# 0X_-_CPU_-_EIM.net
KiCad netlist of a schematic drawn in Altium Designer
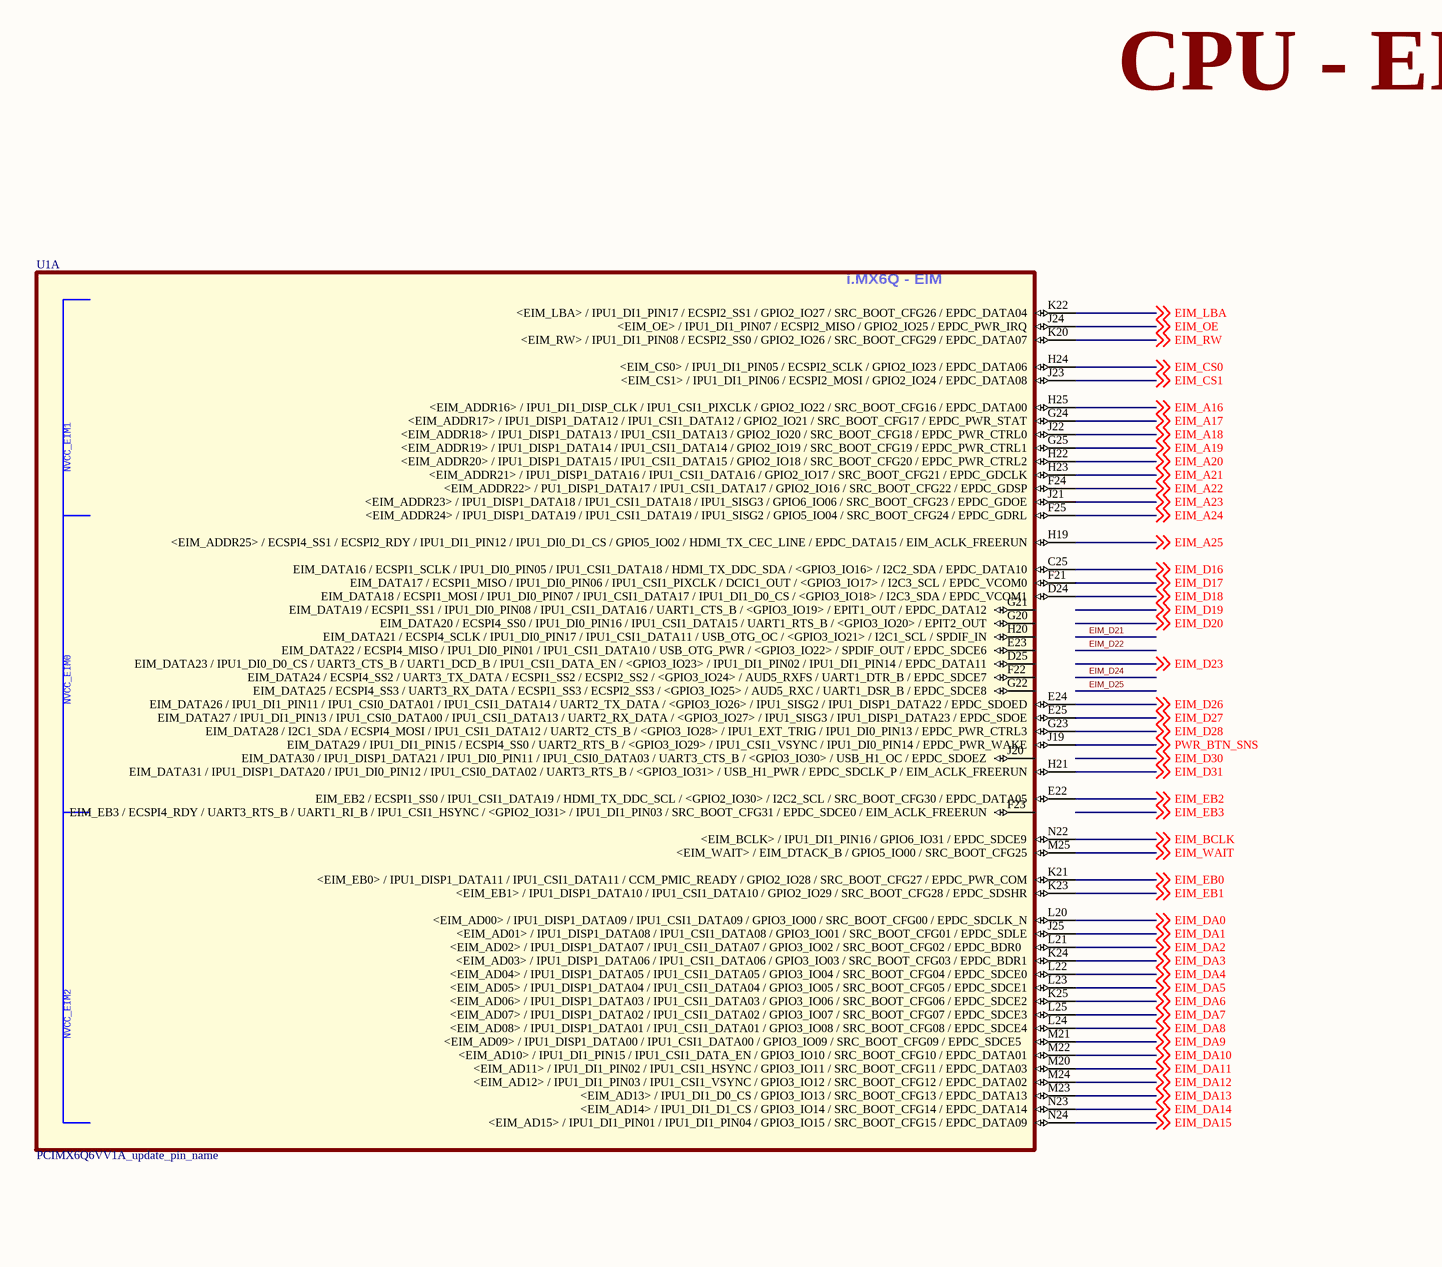
[diagram p0: [0X] - CPU - EIM.SchDoc, left]
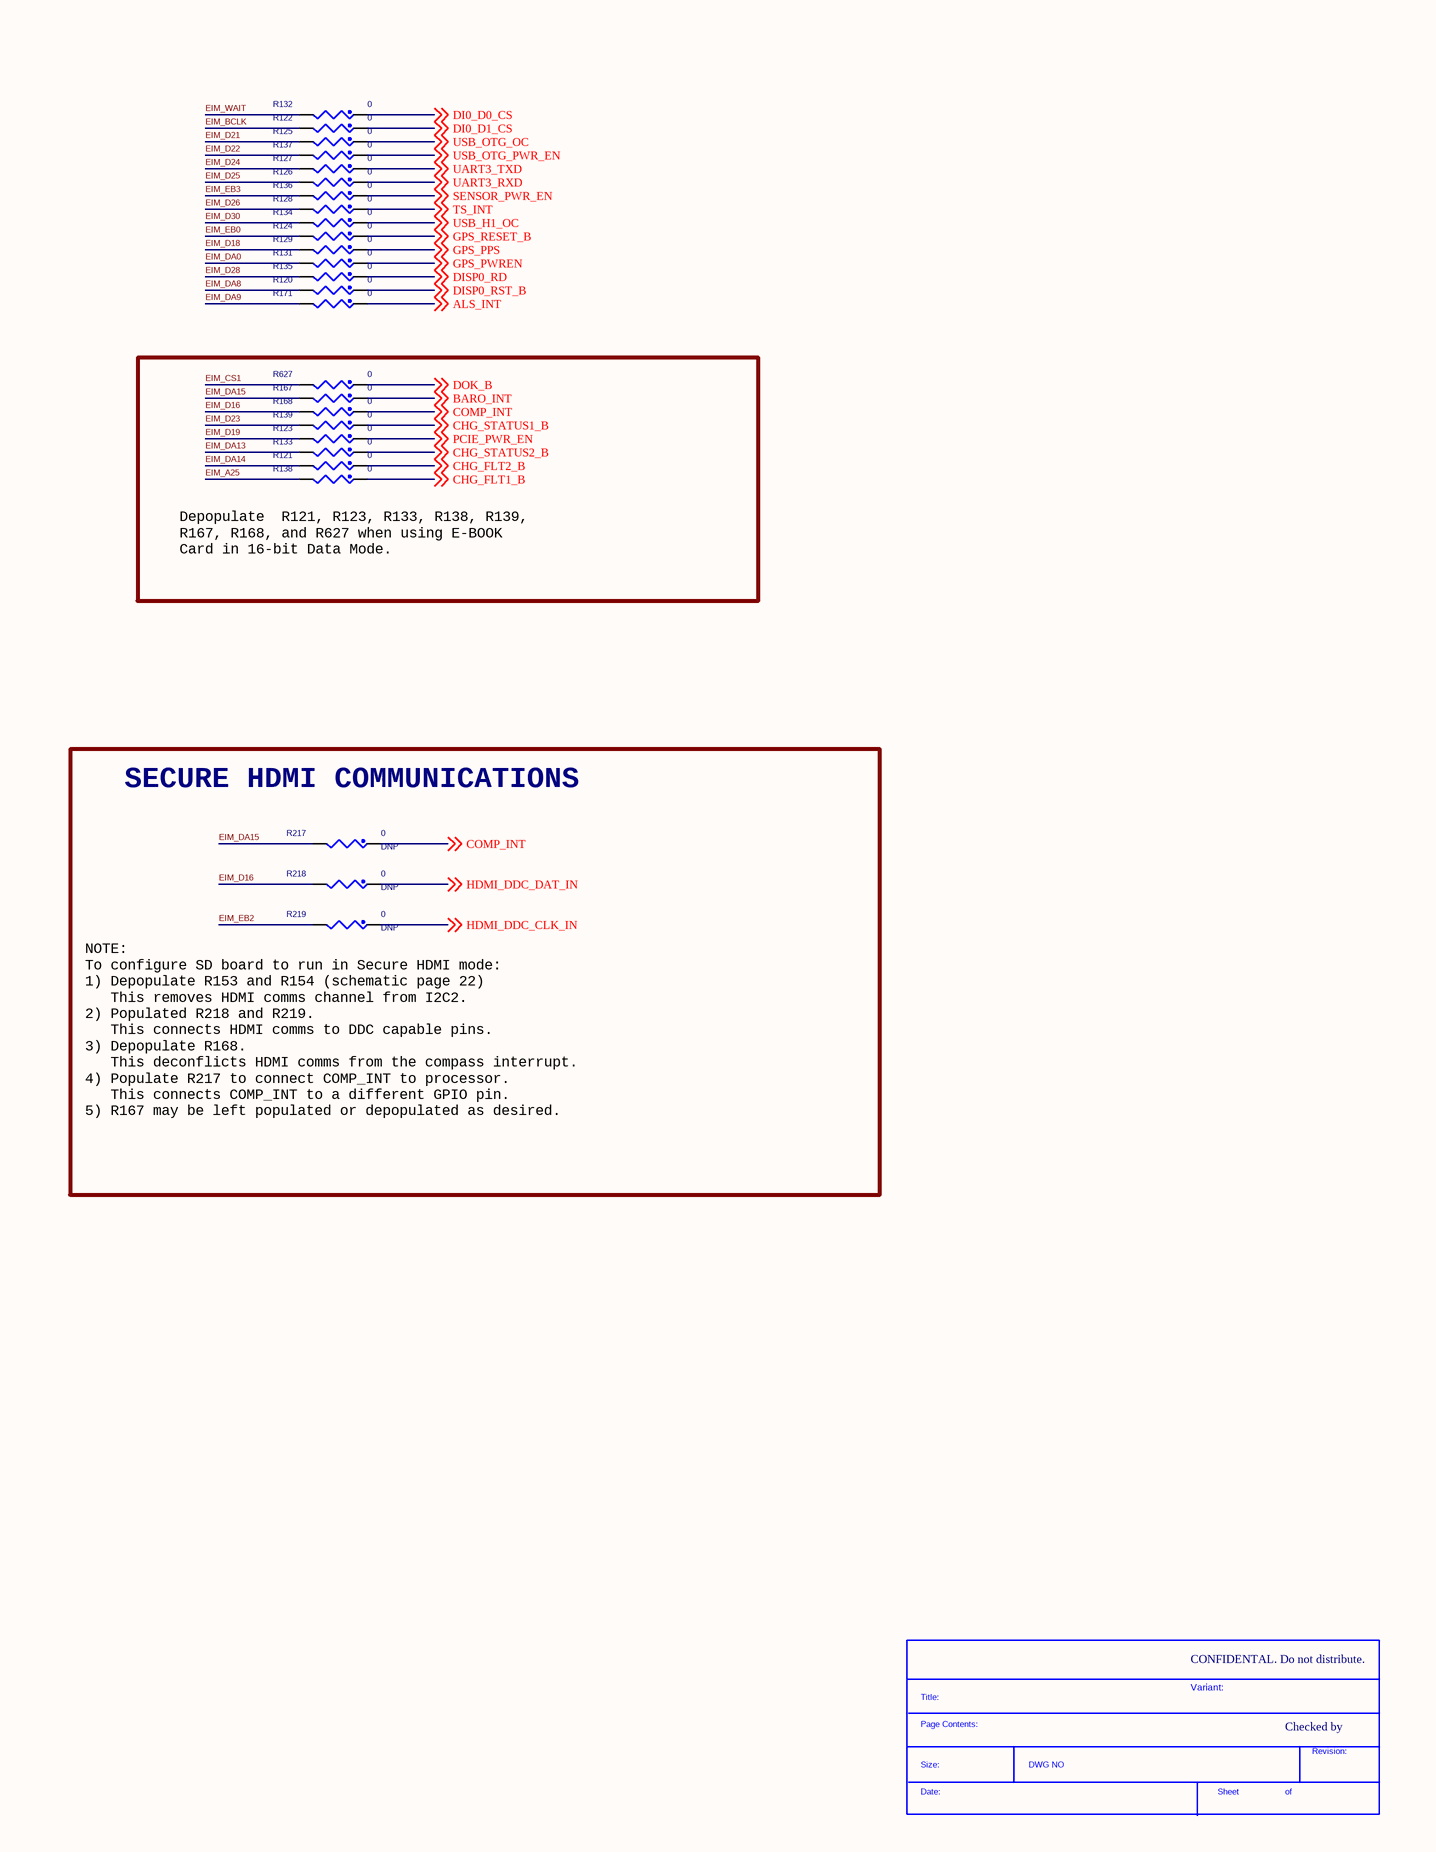
[diagram p1: [0X] - CPU - EIM.SchDoc, right]

(export (version "E")
  (design (tool "Eeschema 10.0.6"))
  (components
    (comp (ref "*") (value "SDTitleBlock") (libsource (lib "*") (part "SDTitleBlock")))
    (comp (ref "R120")
      (value "0")
      (description "RES MF ZERO OHM 1/10W -- 0402")
      (libsource (lib "*") (part "RES"))
    )
    (comp (ref "R121")
      (value "0")
      (description "RES MF ZERO OHM 1/10W -- 0402")
      (libsource (lib "*") (part "RES"))
    )
    (comp (ref "R122")
      (value "0")
      (description "RES MF ZERO OHM 1/10W -- 0402")
      (libsource (lib "*") (part "RES"))
    )
    (comp (ref "R123")
      (value "0")
      (description "RES MF ZERO OHM 1/10W -- 0402")
      (libsource (lib "*") (part "RES"))
    )
    (comp (ref "R124")
      (value "0")
      (description "RES MF ZERO OHM 1/10W -- 0402")
      (libsource (lib "*") (part "RES"))
    )
    (comp (ref "R125")
      (value "0")
      (description "RES MF ZERO OHM 1/10W -- 0402")
      (libsource (lib "*") (part "RES"))
    )
    (comp (ref "R126")
      (value "0")
      (description "RES MF ZERO OHM 1/10W -- 0402")
      (libsource (lib "*") (part "RES"))
    )
    (comp (ref "R127")
      (value "0")
      (description "RES MF ZERO OHM 1/10W -- 0402")
      (libsource (lib "*") (part "RES"))
    )
    (comp (ref "R128")
      (value "0")
      (description "RES MF ZERO OHM 1/10W -- 0402")
      (libsource (lib "*") (part "RES"))
    )
    (comp (ref "R129")
      (value "0")
      (description "RES MF ZERO OHM 1/10W -- 0402")
      (libsource (lib "*") (part "RES"))
    )
    (comp (ref "R131")
      (value "0")
      (description "RES MF ZERO OHM 1/10W -- 0402")
      (libsource (lib "*") (part "RES"))
    )
    (comp (ref "R132")
      (value "0")
      (description "RES MF ZERO OHM 1/10W -- 0402")
      (libsource (lib "*") (part "RES"))
    )
    (comp (ref "R133")
      (value "0")
      (description "RES MF ZERO OHM 1/10W -- 0402")
      (libsource (lib "*") (part "RES"))
    )
    (comp (ref "R134")
      (value "0")
      (description "RES MF ZERO OHM 1/10W -- 0402")
      (libsource (lib "*") (part "RES"))
    )
    (comp (ref "R135")
      (value "0")
      (description "RES MF ZERO OHM 1/10W -- 0402")
      (libsource (lib "*") (part "RES"))
    )
    (comp (ref "R136")
      (value "0")
      (description "RES MF ZERO OHM 1/10W -- 0402")
      (libsource (lib "*") (part "RES"))
    )
    (comp (ref "R137")
      (value "0")
      (description "RES MF ZERO OHM 1/10W -- 0402")
      (libsource (lib "*") (part "RES"))
    )
    (comp (ref "R138")
      (value "0")
      (description "RES MF ZERO OHM 1/10W -- 0402")
      (libsource (lib "*") (part "RES"))
    )
    (comp (ref "R139")
      (value "0")
      (description "RES MF ZERO OHM 1/10W -- 0402")
      (libsource (lib "*") (part "RES"))
    )
    (comp (ref "R167")
      (value "0")
      (description "RES MF ZERO OHM 1/10W -- 0402")
      (libsource (lib "*") (part "RES"))
    )
    (comp (ref "R168")
      (value "0")
      (description "RES MF ZERO OHM 1/10W -- 0402")
      (libsource (lib "*") (part "RES"))
    )
    (comp (ref "R171")
      (value "0")
      (description "RES MF ZERO OHM 1/10W -- 0402")
      (libsource (lib "*") (part "RES"))
    )
    (comp (ref "R217")
      (value "0")
      (description "RES MF ZERO OHM 1/10W -- 0402")
      (fields (field (name "ASSY_OPT") "DNP"))
      (libsource (lib "*") (part "RES"))
    )
    (comp (ref "R218")
      (value "0")
      (description "RES MF ZERO OHM 1/10W -- 0402")
      (fields (field (name "ASSY_OPT") "DNP"))
      (libsource (lib "*") (part "RES"))
    )
    (comp (ref "R219")
      (value "0")
      (description "RES MF ZERO OHM 1/10W -- 0402")
      (fields (field (name "ASSY_OPT") "DNP"))
      (libsource (lib "*") (part "RES"))
    )
    (comp (ref "R627")
      (value "0")
      (description "RES MF ZERO OHM 1/10W -- 0402")
      (libsource (lib "*") (part "RES"))
    )
    (comp (ref "U1")
      (value "PCIMX6Q6VV1A_update_pin_name")
      (libsource (lib "SCH-27516_C3_16_2_Library") (part "PCIMX6Q6VV1A_update_pin_name"))
    )
  )
  (nets
    (net (code "1") (name "/EIM_D21") (class "Default")
      (node (ref "R125") (pin "2") (pinfunction "2_2") (pintype "passive"))
    )
    (net (code "2") (name "/EIM_D22") (class "Default")
      (node (ref "R137") (pin "2") (pinfunction "2_2") (pintype "passive"))
    )
    (net (code "3") (name "/EIM_D24") (class "Default")
      (node (ref "R127") (pin "2") (pinfunction "2_2") (pintype "passive"))
    )
    (net (code "4") (name "/EIM_D25") (class "Default")
      (node (ref "R126") (pin "2") (pinfunction "2_2") (pintype "passive"))
    )
    (net (code "5") (name "ALS_INT") (class "Default")
      (node (ref "R171") (pin "1") (pinfunction "1_1") (pintype "passive"))
    )
    (net (code "6") (name "BARO_INT") (class "Default")
      (node (ref "R167") (pin "1") (pinfunction "1_1") (pintype "passive"))
    )
    (net (code "7") (name "CHG_FLT1_B") (class "Default")
      (node (ref "R138") (pin "1") (pinfunction "1_1") (pintype "passive"))
    )
    (net (code "8") (name "CHG_FLT2_B") (class "Default")
      (node (ref "R121") (pin "1") (pinfunction "1_1") (pintype "passive"))
    )
    (net (code "9") (name "CHG_STATUS1_B") (class "Default")
      (node (ref "R139") (pin "1") (pinfunction "1_1") (pintype "passive"))
    )
    (net (code "10") (name "CHG_STATUS2_B") (class "Default")
      (node (ref "R133") (pin "1") (pinfunction "1_1") (pintype "passive"))
    )
    (net (code "11") (name "COMP_INT") (class "Default")
      (node (ref "R168") (pin "1") (pinfunction "1_1") (pintype "passive"))
      (node (ref "R217") (pin "1") (pinfunction "1_1") (pintype "passive"))
    )
    (net (code "12") (name "DI0_D0_CS") (class "Default")
      (node (ref "R132") (pin "1") (pinfunction "1_1") (pintype "passive"))
    )
    (net (code "13") (name "DI0_D1_CS") (class "Default")
      (node (ref "R122") (pin "1") (pinfunction "1_1") (pintype "passive"))
    )
    (net (code "14") (name "DISP0_RD") (class "Default")
      (node (ref "R135") (pin "1") (pinfunction "1_1") (pintype "passive"))
    )
    (net (code "15") (name "DISP0_RST_B") (class "Default")
      (node (ref "R120") (pin "1") (pinfunction "1_1") (pintype "passive"))
    )
    (net (code "16") (name "DOK_B") (class "Default")
      (node (ref "R627") (pin "1") (pinfunction "1_1") (pintype "passive"))
    )
    (net (code "17") (name "EIM_A16") (class "Default")
      (node (ref "U1") (pin "H25") (pinfunction "<EIM_ADDR16>_/_IPU1_DI1_DISP_CLK_/_IPU1_CSI1_PIXCLK_/_GPIO2_IO22_/_SRC_BOOT_CFG16_/_EPDC_DATA00_H25") (pintype "bidirectional"))
    )
    (net (code "18") (name "EIM_A17") (class "Default")
      (node (ref "U1") (pin "G24") (pinfunction "<EIM_ADDR17>_/_IPU1_DISP1_DATA12_/_IPU1_CSI1_DATA12_/_GPIO2_IO21_/_SRC_BOOT_CFG17_/_EPDC_PWR_STAT_G24") (pintype "bidirectional"))
    )
    (net (code "19") (name "EIM_A18") (class "Default")
      (node (ref "U1") (pin "J22") (pinfunction "<EIM_ADDR18>_/_IPU1_DISP1_DATA13_/_IPU1_CSI1_DATA13_/_GPIO2_IO20_/_SRC_BOOT_CFG18_/_EPDC_PWR_CTRL0_J22") (pintype "bidirectional"))
    )
    (net (code "20") (name "EIM_A19") (class "Default")
      (node (ref "U1") (pin "G25") (pinfunction "__<EIM_ADDR19>_/_IPU1_DISP1_DATA14_/_IPU1_CSI1_DATA14_/_GPIO2_IO19_/_SRC_BOOT_CFG19_/_EPDC_PWR_CTRL1_G25") (pintype "bidirectional"))
    )
    (net (code "21") (name "EIM_A20") (class "Default")
      (node (ref "U1") (pin "H22") (pinfunction "<EIM_ADDR20>_/_IPU1_DISP1_DATA15_/_IPU1_CSI1_DATA15_/_GPIO2_IO18_/_SRC_BOOT_CFG20_/_EPDC_PWR_CTRL2_H22") (pintype "bidirectional"))
    )
    (net (code "22") (name "EIM_A21") (class "Default")
      (node (ref "U1") (pin "H23") (pinfunction "<EIM_ADDR21>_/_IPU1_DISP1_DATA16_/_IPU1_CSI1_DATA16_/_GPIO2_IO17_/_SRC_BOOT_CFG21_/_EPDC_GDCLK_H23") (pintype "bidirectional"))
    )
    (net (code "23") (name "EIM_A22") (class "Default")
      (node (ref "U1") (pin "F24") (pinfunction "<EIM_ADDR22>_/_PU1_DISP1_DATA17_/_IPU1_CSI1_DATA17_/_GPIO2_IO16_/_SRC_BOOT_CFG22_/_EPDC_GDSP_F24") (pintype "bidirectional"))
    )
    (net (code "24") (name "EIM_A23") (class "Default")
      (node (ref "U1") (pin "J21") (pinfunction "<EIM_ADDR23>_/_IPU1_DISP1_DATA18_/_IPU1_CSI1_DATA18_/_IPU1_SISG3_/_GPIO6_IO06_/_SRC_BOOT_CFG23_/_EPDC_GDOE_J21") (pintype "bidirectional"))
    )
    (net (code "25") (name "EIM_A24") (class "Default")
      (node (ref "U1") (pin "F25") (pinfunction "<EIM_ADDR24>_/_IPU1_DISP1_DATA19_/_IPU1_CSI1_DATA19_/_IPU1_SISG2_/_GPIO5_IO04_/_SRC_BOOT_CFG24_/_EPDC_GDRL_F25") (pintype "bidirectional"))
    )
    (net (code "26") (name "EIM_A25") (class "Default")
      (node (ref "R138") (pin "2") (pinfunction "2_2") (pintype "passive"))
      (node (ref "U1") (pin "H19") (pinfunction "<EIM_ADDR25>_/_ECSPI4_SS1_/_ECSPI2_RDY_/_IPU1_DI1_PIN12_/_IPU1_DI0_D1_CS_/_GPIO5_IO02_/_HDMI_TX_CEC_LINE_/_EPDC_DATA15_/_EIM_ACLK_FREERUN_H19") (pintype "bidirectional"))
    )
    (net (code "27") (name "EIM_BCLK") (class "Default")
      (node (ref "R122") (pin "2") (pinfunction "2_2") (pintype "passive"))
      (node (ref "U1") (pin "N22") (pinfunction "<EIM_BCLK>_/_IPU1_DI1_PIN16_/_GPIO6_IO31_/_EPDC_SDCE9_N22") (pintype "bidirectional"))
    )
    (net (code "28") (name "EIM_CS0") (class "Default")
      (node (ref "U1") (pin "H24") (pinfunction "<EIM_CS0>_/_IPU1_DI1_PIN05_/_ECSPI2_SCLK_/_GPIO2_IO23_/_EPDC_DATA06_H24") (pintype "bidirectional"))
    )
    (net (code "29") (name "EIM_CS1") (class "Default")
      (node (ref "R627") (pin "2") (pinfunction "2_2") (pintype "passive"))
      (node (ref "U1") (pin "J23") (pinfunction "<EIM_CS1>_/_IPU1_DI1_PIN06_/_ECSPI2_MOSI_/_GPIO2_IO24_/_EPDC_DATA08_J23") (pintype "bidirectional"))
    )
    (net (code "30") (name "EIM_D16") (class "Default")
      (node (ref "R168") (pin "2") (pinfunction "2_2") (pintype "passive"))
      (node (ref "R218") (pin "2") (pinfunction "2_2") (pintype "passive"))
      (node (ref "U1") (pin "C25") (pinfunction "EIM_DATA16_/_ECSPI1_SCLK_/_IPU1_DI0_PIN05_/_IPU1_CSI1_DATA18_/_HDMI_TX_DDC_SDA_/_<GPIO3_IO16>_/_I2C2_SDA_/_EPDC_DATA10_C25") (pintype "bidirectional"))
    )
    (net (code "31") (name "EIM_D17") (class "Default")
      (node (ref "U1") (pin "F21") (pinfunction "EIM_DATA17_/_ECSPI1_MISO_/_IPU1_DI0_PIN06_/_IPU1_CSI1_PIXCLK_/_DCIC1_OUT_/_<GPIO3_IO17>_/_I2C3_SCL_/_EPDC_VCOM0_F21") (pintype "bidirectional"))
    )
    (net (code "32") (name "EIM_D18") (class "Default")
      (node (ref "R129") (pin "2") (pinfunction "2_2") (pintype "passive"))
      (node (ref "U1") (pin "D24") (pinfunction "EIM_DATA18_/_ECSPI1_MOSI_/_IPU1_DI0_PIN07_/_IPU1_CSI1_DATA17_/_IPU1_DI1_D0_CS_/_<GPIO3_IO18>_/_I2C3_SDA_/_EPDC_VCOM1_D24") (pintype "bidirectional"))
    )
    (net (code "33") (name "EIM_D19") (class "Default")
      (node (ref "R123") (pin "2") (pinfunction "2_2") (pintype "passive"))
    )
    (net (code "35") (name "EIM_D23") (class "Default")
      (node (ref "R139") (pin "2") (pinfunction "2_2") (pintype "passive"))
    )
    (net (code "36") (name "EIM_D26") (class "Default")
      (node (ref "R128") (pin "2") (pinfunction "2_2") (pintype "passive"))
      (node (ref "U1") (pin "E24") (pinfunction "EIM_DATA26_/_IPU1_DI1_PIN11_/_IPU1_CSI0_DATA01_/_IPU1_CSI1_DATA14_/_UART2_TX_DATA_/_<GPIO3_IO26>_/_IPU1_SISG2_/_IPU1_DISP1_DATA22_/_EPDC_SDOED_E24") (pintype "bidirectional"))
    )
    (net (code "37") (name "EIM_D27") (class "Default")
      (node (ref "U1") (pin "E25") (pinfunction "EIM_DATA27_/_IPU1_DI1_PIN13_/_IPU1_CSI0_DATA00_/_IPU1_CSI1_DATA13_/_UART2_RX_DATA_/_<GPIO3_IO27>_/_IPU1_SISG3_/_IPU1_DISP1_DATA23_/_EPDC_SDOE_E25") (pintype "bidirectional"))
    )
    (net (code "38") (name "EIM_D28") (class "Default")
      (node (ref "R135") (pin "2") (pinfunction "2_2") (pintype "passive"))
      (node (ref "U1") (pin "G23") (pinfunction "EIM_DATA28_/_I2C1_SDA_/_ECSPI4_MOSI_/_IPU1_CSI1_DATA12_/_UART2_CTS_B_/_<GPIO3_IO28>_/_IPU1_EXT_TRIG_/_IPU1_DI0_PIN13_/_EPDC_PWR_CTRL3_G23") (pintype "bidirectional"))
    )
    (net (code "39") (name "EIM_D30") (class "Default")
      (node (ref "R134") (pin "2") (pinfunction "2_2") (pintype "passive"))
    )
    (net (code "40") (name "EIM_D31") (class "Default")
      (node (ref "U1") (pin "H21") (pinfunction "EIM_DATA31_/_IPU1_DISP1_DATA20_/_IPU1_DI0_PIN12_/_IPU1_CSI0_DATA02_/_UART3_RTS_B_/_<GPIO3_IO31>_/_USB_H1_PWR_/_EPDC_SDCLK_P_/_EIM_ACLK_FREERUN_H21") (pintype "bidirectional"))
    )
    (net (code "41") (name "EIM_DA0") (class "Default")
      (node (ref "R131") (pin "2") (pinfunction "2_2") (pintype "passive"))
      (node (ref "U1") (pin "L20") (pinfunction "<EIM_AD00>_/_IPU1_DISP1_DATA09_/_IPU1_CSI1_DATA09_/_GPIO3_IO00_/_SRC_BOOT_CFG00_/_EPDC_SDCLK_N_L20") (pintype "bidirectional"))
    )
    (net (code "42") (name "EIM_DA1") (class "Default")
      (node (ref "U1") (pin "J25") (pinfunction "<EIM_AD01>_/_IPU1_DISP1_DATA08_/_IPU1_CSI1_DATA08_/_GPIO3_IO01_/_SRC_BOOT_CFG01_/_EPDC_SDLE_J25") (pintype "bidirectional"))
    )
    (net (code "43") (name "EIM_DA2") (class "Default")
      (node (ref "U1") (pin "L21") (pinfunction "__<EIM_AD02>_/_IPU1_DISP1_DATA07_/_IPU1_CSI1_DATA07_/_GPIO3_IO02_/_SRC_BOOT_CFG02_/_EPDC_BDR0_L21") (pintype "bidirectional"))
    )
    (net (code "44") (name "EIM_DA3") (class "Default")
      (node (ref "U1") (pin "K24") (pinfunction "<EIM_AD03>_/_IPU1_DISP1_DATA06_/_IPU1_CSI1_DATA06_/_GPIO3_IO03_/_SRC_BOOT_CFG03_/_EPDC_BDR1_K24") (pintype "bidirectional"))
    )
    (net (code "45") (name "EIM_DA4") (class "Default")
      (node (ref "U1") (pin "L22") (pinfunction "<EIM_AD04>_/_IPU1_DISP1_DATA05_/_IPU1_CSI1_DATA05_/_GPIO3_IO04_/_SRC_BOOT_CFG04_/_EPDC_SDCE0_L22") (pintype "bidirectional"))
    )
    (net (code "46") (name "EIM_DA5") (class "Default")
      (node (ref "U1") (pin "L23") (pinfunction "<EIM_AD05>_/_IPU1_DISP1_DATA04_/_IPU1_CSI1_DATA04_/_GPIO3_IO05_/_SRC_BOOT_CFG05_/_EPDC_SDCE1_L23") (pintype "bidirectional"))
    )
    (net (code "47") (name "EIM_DA6") (class "Default")
      (node (ref "U1") (pin "K25") (pinfunction "<EIM_AD06>_/_IPU1_DISP1_DATA03_/_IPU1_CSI1_DATA03_/_GPIO3_IO06_/_SRC_BOOT_CFG06_/_EPDC_SDCE2_K25") (pintype "bidirectional"))
    )
    (net (code "48") (name "EIM_DA7") (class "Default")
      (node (ref "U1") (pin "L25") (pinfunction "__<EIM_AD07>_/_IPU1_DISP1_DATA02_/_IPU1_CSI1_DATA02_/_GPIO3_IO07_/_SRC_BOOT_CFG07_/_EPDC_SDCE3_L25") (pintype "bidirectional"))
    )
    (net (code "49") (name "EIM_DA8") (class "Default")
      (node (ref "R120") (pin "2") (pinfunction "2_2") (pintype "passive"))
      (node (ref "U1") (pin "L24") (pinfunction "<EIM_AD08>_/_IPU1_DISP1_DATA01_/_IPU1_CSI1_DATA01_/_GPIO3_IO08_/_SRC_BOOT_CFG08_/_EPDC_SDCE4_L24") (pintype "bidirectional"))
    )
    (net (code "50") (name "EIM_DA9") (class "Default")
      (node (ref "R171") (pin "2") (pinfunction "2_2") (pintype "passive"))
      (node (ref "U1") (pin "M21") (pinfunction "__<EIM_AD09>_/_IPU1_DISP1_DATA00_/_IPU1_CSI1_DATA00_/_GPIO3_IO09_/_SRC_BOOT_CFG09_/_EPDC_SDCE5_M21") (pintype "bidirectional"))
    )
    (net (code "51") (name "EIM_DA10") (class "Default")
      (node (ref "U1") (pin "M22") (pinfunction "__<EIM_AD10>_/_IPU1_DI1_PIN15_/_IPU1_CSI1_DATA_EN_/_GPIO3_IO10_/_SRC_BOOT_CFG10_/_EPDC_DATA01_M22") (pintype "bidirectional"))
    )
    (net (code "52") (name "EIM_DA11") (class "Default")
      (node (ref "U1") (pin "M20") (pinfunction "__<EIM_AD11>_/_IPU1_DI1_PIN02_/_IPU1_CSI1_HSYNC_/_GPIO3_IO11_/_SRC_BOOT_CFG11_/_EPDC_DATA03_M20") (pintype "bidirectional"))
    )
    (net (code "53") (name "EIM_DA12") (class "Default")
      (node (ref "U1") (pin "M24") (pinfunction "<EIM_AD12>_/_IPU1_DI1_PIN03_/_IPU1_CSI1_VSYNC_/_GPIO3_IO12_/_SRC_BOOT_CFG12_/_EPDC_DATA02_M24") (pintype "bidirectional"))
    )
    (net (code "54") (name "EIM_DA13") (class "Default")
      (node (ref "R133") (pin "2") (pinfunction "2_2") (pintype "passive"))
      (node (ref "U1") (pin "M23") (pinfunction "<EIM_AD13>_/_IPU1_DI1_D0_CS_/_GPIO3_IO13_/_SRC_BOOT_CFG13_/_EPDC_DATA13_M23") (pintype "bidirectional"))
    )
    (net (code "55") (name "EIM_DA14") (class "Default")
      (node (ref "R121") (pin "2") (pinfunction "2_2") (pintype "passive"))
      (node (ref "U1") (pin "N23") (pinfunction "<EIM_AD14>_/_IPU1_DI1_D1_CS_/_GPIO3_IO14_/_SRC_BOOT_CFG14_/_EPDC_DATA14_N23") (pintype "bidirectional"))
    )
    (net (code "56") (name "EIM_DA15") (class "Default")
      (node (ref "R167") (pin "2") (pinfunction "2_2") (pintype "passive"))
      (node (ref "R217") (pin "2") (pinfunction "2_2") (pintype "passive"))
      (node (ref "U1") (pin "N24") (pinfunction "<EIM_AD15>_/_IPU1_DI1_PIN01_/_IPU1_DI1_PIN04_/_GPIO3_IO15_/_SRC_BOOT_CFG15_/_EPDC_DATA09_N24") (pintype "bidirectional"))
    )
    (net (code "57") (name "EIM_EB0") (class "Default")
      (node (ref "R124") (pin "2") (pinfunction "2_2") (pintype "passive"))
      (node (ref "U1") (pin "K21") (pinfunction "<EIM_EB0>_/_IPU1_DISP1_DATA11_/_IPU1_CSI1_DATA11_/_CCM_PMIC_READY_/_GPIO2_IO28_/_SRC_BOOT_CFG27_/_EPDC_PWR_COM_K21") (pintype "bidirectional"))
    )
    (net (code "58") (name "EIM_EB1") (class "Default")
      (node (ref "U1") (pin "K23") (pinfunction "<EIM_EB1>_/_IPU1_DISP1_DATA10_/_IPU1_CSI1_DATA10_/_GPIO2_IO29_/_SRC_BOOT_CFG28_/_EPDC_SDSHR_K23") (pintype "bidirectional"))
    )
    (net (code "59") (name "EIM_EB2") (class "Default")
      (node (ref "R219") (pin "2") (pinfunction "2_2") (pintype "passive"))
      (node (ref "U1") (pin "E22") (pinfunction "__EIM_EB2_/_ECSPI1_SS0_/_IPU1_CSI1_DATA19_/_HDMI_TX_DDC_SCL_/_<GPIO2_IO30>_/_I2C2_SCL_/_SRC_BOOT_CFG30_/_EPDC_DATA05_E22") (pintype "bidirectional"))
    )
    (net (code "60") (name "EIM_EB3") (class "Default")
      (node (ref "R136") (pin "2") (pinfunction "2_2") (pintype "passive"))
    )
    (net (code "61") (name "EIM_LBA") (class "Default")
      (node (ref "U1") (pin "K22") (pinfunction "<EIM_LBA>_/_IPU1_DI1_PIN17_/_ECSPI2_SS1_/_GPIO2_IO27_/_SRC_BOOT_CFG26_/_EPDC_DATA04_K22") (pintype "bidirectional"))
    )
    (net (code "62") (name "EIM_OE") (class "Default")
      (node (ref "U1") (pin "J24") (pinfunction "<EIM_OE>_/_IPU1_DI1_PIN07_/_ECSPI2_MISO_/_GPIO2_IO25_/_EPDC_PWR_IRQ_J24") (pintype "bidirectional"))
    )
    (net (code "63") (name "EIM_RW") (class "Default")
      (node (ref "U1") (pin "K20") (pinfunction "__<EIM_RW>_/_IPU1_DI1_PIN08_/_ECSPI2_SS0_/_GPIO2_IO26_/_SRC_BOOT_CFG29_/_EPDC_DATA07_K20") (pintype "bidirectional"))
    )
    (net (code "64") (name "EIM_WAIT") (class "Default")
      (node (ref "R132") (pin "2") (pinfunction "2_2") (pintype "passive"))
      (node (ref "U1") (pin "M25") (pinfunction "<EIM_WAIT>_/_EIM_DTACK_B_/_GPIO5_IO00_/_SRC_BOOT_CFG25_M25") (pintype "bidirectional"))
    )
    (net (code "65") (name "GPS_PPS") (class "Default")
      (node (ref "R129") (pin "1") (pinfunction "1_1") (pintype "passive"))
    )
    (net (code "66") (name "GPS_PWREN") (class "Default")
      (node (ref "R131") (pin "1") (pinfunction "1_1") (pintype "passive"))
    )
    (net (code "67") (name "GPS_RESET_B") (class "Default")
      (node (ref "R124") (pin "1") (pinfunction "1_1") (pintype "passive"))
    )
    (net (code "68") (name "HDMI_DDC_CLK_IN") (class "Default")
      (node (ref "R219") (pin "1") (pinfunction "1_1") (pintype "passive"))
    )
    (net (code "69") (name "HDMI_DDC_DAT_IN") (class "Default")
      (node (ref "R218") (pin "1") (pinfunction "1_1") (pintype "passive"))
    )
    (net (code "70") (name "PCIE_PWR_EN") (class "Default")
      (node (ref "R123") (pin "1") (pinfunction "1_1") (pintype "passive"))
    )
    (net (code "71") (name "PWR_BTN_SNS") (class "Default")
      (node (ref "U1") (pin "J19") (pinfunction "EIM_DATA29_/_IPU1_DI1_PIN15_/_ECSPI4_SS0_/_UART2_RTS_B_/_<GPIO3_IO29>_/_IPU1_CSI1_VSYNC_/_IPU1_DI0_PIN14_/_EPDC_PWR_WAKE_J19") (pintype "bidirectional"))
    )
    (net (code "72") (name "SENSOR_PWR_EN") (class "Default")
      (node (ref "R136") (pin "1") (pinfunction "1_1") (pintype "passive"))
    )
    (net (code "73") (name "TS_INT") (class "Default")
      (node (ref "R128") (pin "1") (pinfunction "1_1") (pintype "passive"))
    )
    (net (code "74") (name "UART3_RXD") (class "Default")
      (node (ref "R126") (pin "1") (pinfunction "1_1") (pintype "passive"))
    )
    (net (code "75") (name "UART3_TXD") (class "Default")
      (node (ref "R127") (pin "1") (pinfunction "1_1") (pintype "passive"))
    )
    (net (code "76") (name "USB_H1_OC") (class "Default")
      (node (ref "R134") (pin "1") (pinfunction "1_1") (pintype "passive"))
    )
    (net (code "77") (name "USB_OTG_OC") (class "Default")
      (node (ref "R125") (pin "1") (pinfunction "1_1") (pintype "passive"))
    )
    (net (code "78") (name "USB_OTG_PWR_EN") (class "Default")
      (node (ref "R137") (pin "1") (pinfunction "1_1") (pintype "passive"))
    )
    (net (code "79") (name "unconnected-(U1A-EIM_DATA20_{slash}_ECSPI4_SS0_{slash}_IPU1_DI0_PIN16_{slash}_IPU1_CSI1_DATA15_{slash}_UART1_RTS_B_{slash}_<GPIO3_IO20>_{slash}_EPIT2_OUT-PadG20)") (class "Default")
      (node (ref "U1") (pin "G20") (pinfunction "EIM_DATA20_/_ECSPI4_SS0_/_IPU1_DI0_PIN16_/_IPU1_CSI1_DATA15_/_UART1_RTS_B_/_<GPIO3_IO20>_/_EPIT2_OUT_G20") (pintype "bidirectional"))
    )
    (net (code "80") (name "unconnected-(U1A-EIM_DATA21_{slash}_ECSPI4_SCLK_{slash}_IPU1_DI0_PIN17_{slash}_IPU1_CSI1_DATA11_{slash}_USB_OTG_OC_{slash}_<GPIO3_IO21>_{slash}_I2C1_SCL_{slash}_SPDIF_IN-PadH20)") (class "Default")
      (node (ref "U1") (pin "H20") (pinfunction "EIM_DATA21_/_ECSPI4_SCLK_/_IPU1_DI0_PIN17_/_IPU1_CSI1_DATA11_/_USB_OTG_OC_/_<GPIO3_IO21>_/_I2C1_SCL_/_SPDIF_IN_H20") (pintype "bidirectional"))
    )
    (net (code "81") (name "unconnected-(U1A-EIM_DATA23_{slash}_IPU1_DI0_D0_CS_{slash}_UART3_CTS_B_{slash}_UART1_DCD_B_{slash}_IPU1_CSI1_DATA_EN_{slash}_<GPIO3_IO23>_{slash}_IPU1_DI1_PIN02_{slash}_IPU1_DI1_PIN14_{slash}_EPDC_DATA11-PadD25)") (class "Default")
      (node (ref "U1") (pin "D25") (pinfunction "EIM_DATA23_/_IPU1_DI0_D0_CS_/_UART3_CTS_B_/_UART1_DCD_B_/_IPU1_CSI1_DATA_EN_/_<GPIO3_IO23>_/_IPU1_DI1_PIN02_/_IPU1_DI1_PIN14_/_EPDC_DATA11_D25") (pintype "bidirectional"))
    )
    (net (code "82") (name "unconnected-(U1A-EIM_EB3_{slash}_ECSPI4_RDY_{slash}_UART3_RTS_B_{slash}_UART1_RI_B_{slash}_IPU1_CSI1_HSYNC_{slash}_<GPIO2_IO31>_{slash}_IPU1_DI1_PIN03_{slash}_SRC_BOOT_CFG31_{slash}_EPDC_SDCE0_{slash}_EIM_ACLK_FREERUN-PadF23)") (class "Default")
      (node (ref "U1") (pin "F23") (pinfunction "EIM_EB3_/_ECSPI4_RDY_/_UART3_RTS_B_/_UART1_RI_B_/_IPU1_CSI1_HSYNC_/_<GPIO2_IO31>_/_IPU1_DI1_PIN03_/_SRC_BOOT_CFG31_/_EPDC_SDCE0_/_EIM_ACLK_FREERUN_F23") (pintype "bidirectional"))
    )
    (net (code "83") (name "unconnected-(U1A-__EIM_DATA19_{slash}_ECSPI1_SS1_{slash}_IPU1_DI0_PIN08_{slash}_IPU1_CSI1_DATA16_{slash}_UART1_CTS_B_{slash}_<GPIO3_IO19>_{slash}_EPIT1_OUT_{slash}_EPDC_DATA12-PadG21)") (class "Default")
      (node (ref "U1") (pin "G21") (pinfunction "__EIM_DATA19_/_ECSPI1_SS1_/_IPU1_DI0_PIN08_/_IPU1_CSI1_DATA16_/_UART1_CTS_B_/_<GPIO3_IO19>_/_EPIT1_OUT_/_EPDC_DATA12_G21") (pintype "bidirectional"))
    )
    (net (code "84") (name "unconnected-(U1A-__EIM_DATA22_{slash}_ECSPI4_MISO_{slash}_IPU1_DI0_PIN01_{slash}_IPU1_CSI1_DATA10_{slash}_USB_OTG_PWR_{slash}_<GPIO3_IO22>_{slash}_SPDIF_OUT_{slash}_EPDC_SDCE6-PadE23)") (class "Default")
      (node (ref "U1") (pin "E23") (pinfunction "__EIM_DATA22_/_ECSPI4_MISO_/_IPU1_DI0_PIN01_/_IPU1_CSI1_DATA10_/_USB_OTG_PWR_/_<GPIO3_IO22>_/_SPDIF_OUT_/_EPDC_SDCE6_E23") (pintype "bidirectional"))
    )
    (net (code "85") (name "unconnected-(U1A-__EIM_DATA24_{slash}_ECSPI4_SS2_{slash}_UART3_TX_DATA_{slash}_ECSPI1_SS2_{slash}_ECSPI2_SS2_{slash}_<GPIO3_IO24>_{slash}_AUD5_RXFS_{slash}_UART1_DTR_B_{slash}_EPDC_SDCE7-PadF22)") (class "Default")
      (node (ref "U1") (pin "F22") (pinfunction "__EIM_DATA24_/_ECSPI4_SS2_/_UART3_TX_DATA_/_ECSPI1_SS2_/_ECSPI2_SS2_/_<GPIO3_IO24>_/_AUD5_RXFS_/_UART1_DTR_B_/_EPDC_SDCE7_F22") (pintype "bidirectional"))
    )
    (net (code "86") (name "unconnected-(U1A-__EIM_DATA25_{slash}_ECSPI4_SS3_{slash}_UART3_RX_DATA_{slash}_ECSPI1_SS3_{slash}_ECSPI2_SS3_{slash}_<GPIO3_IO25>_{slash}_AUD5_RXC_{slash}_UART1_DSR_B_{slash}_EPDC_SDCE8-PadG22)") (class "Default")
      (node (ref "U1") (pin "G22") (pinfunction "__EIM_DATA25_/_ECSPI4_SS3_/_UART3_RX_DATA_/_ECSPI1_SS3_/_ECSPI2_SS3_/_<GPIO3_IO25>_/_AUD5_RXC_/_UART1_DSR_B_/_EPDC_SDCE8_G22") (pintype "bidirectional"))
    )
    (net (code "87") (name "unconnected-(U1A-__EIM_DATA30_{slash}_IPU1_DISP1_DATA21_{slash}_IPU1_DI0_PIN11_{slash}_IPU1_CSI0_DATA03_{slash}_UART3_CTS_B_{slash}_<GPIO3_IO30>_{slash}_USB_H1_OC_{slash}_EPDC_SDOEZ-PadJ20)") (class "Default")
      (node (ref "U1") (pin "J20") (pinfunction "__EIM_DATA30_/_IPU1_DISP1_DATA21_/_IPU1_DI0_PIN11_/_IPU1_CSI0_DATA03_/_UART3_CTS_B_/_<GPIO3_IO30>_/_USB_H1_OC_/_EPDC_SDOEZ_J20") (pintype "bidirectional"))
    )
  )
)
